# Mainboard.net
KiCad netlist of a schematic drawn in EAGLE
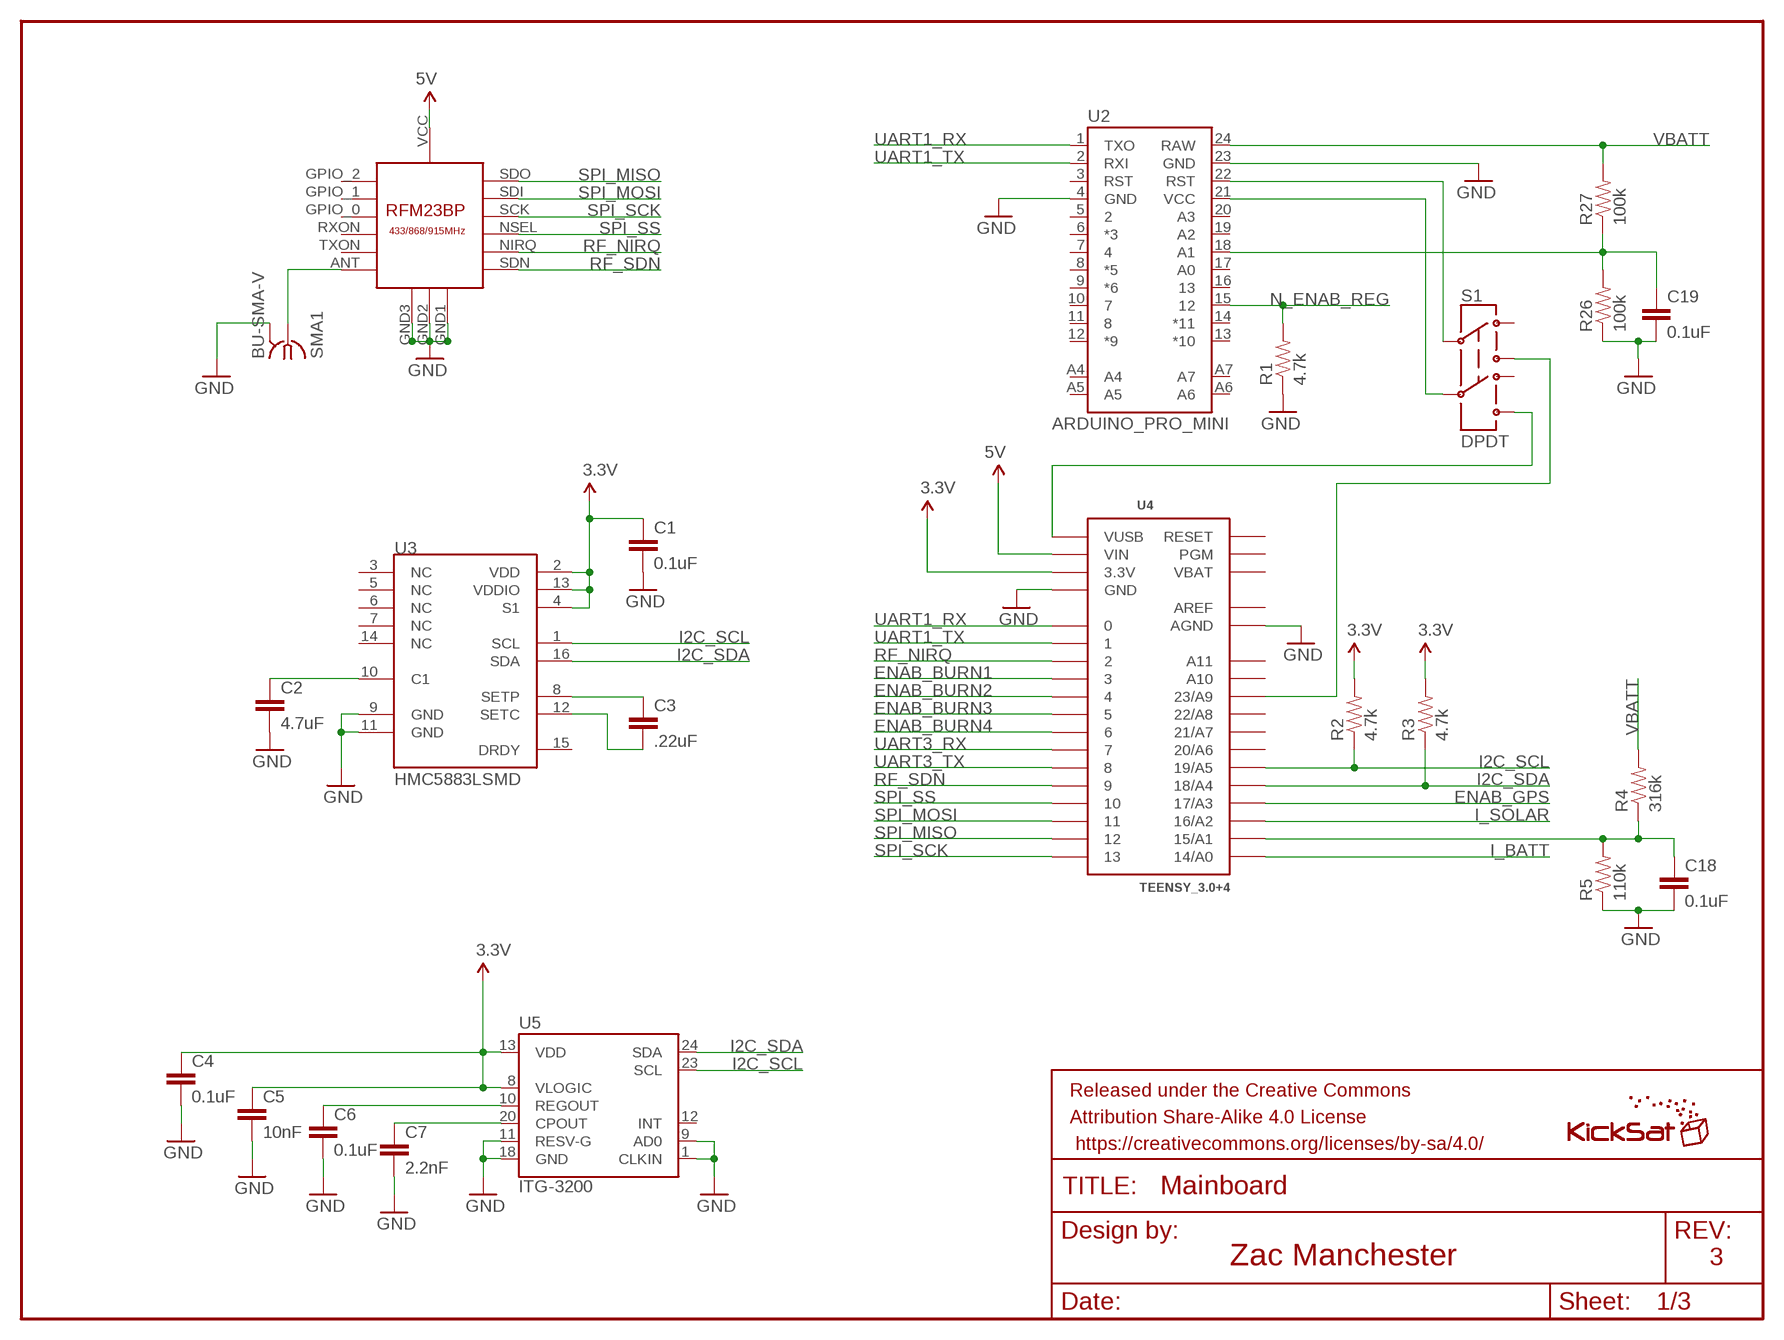
[diagram p0: schematic, sheet 1]
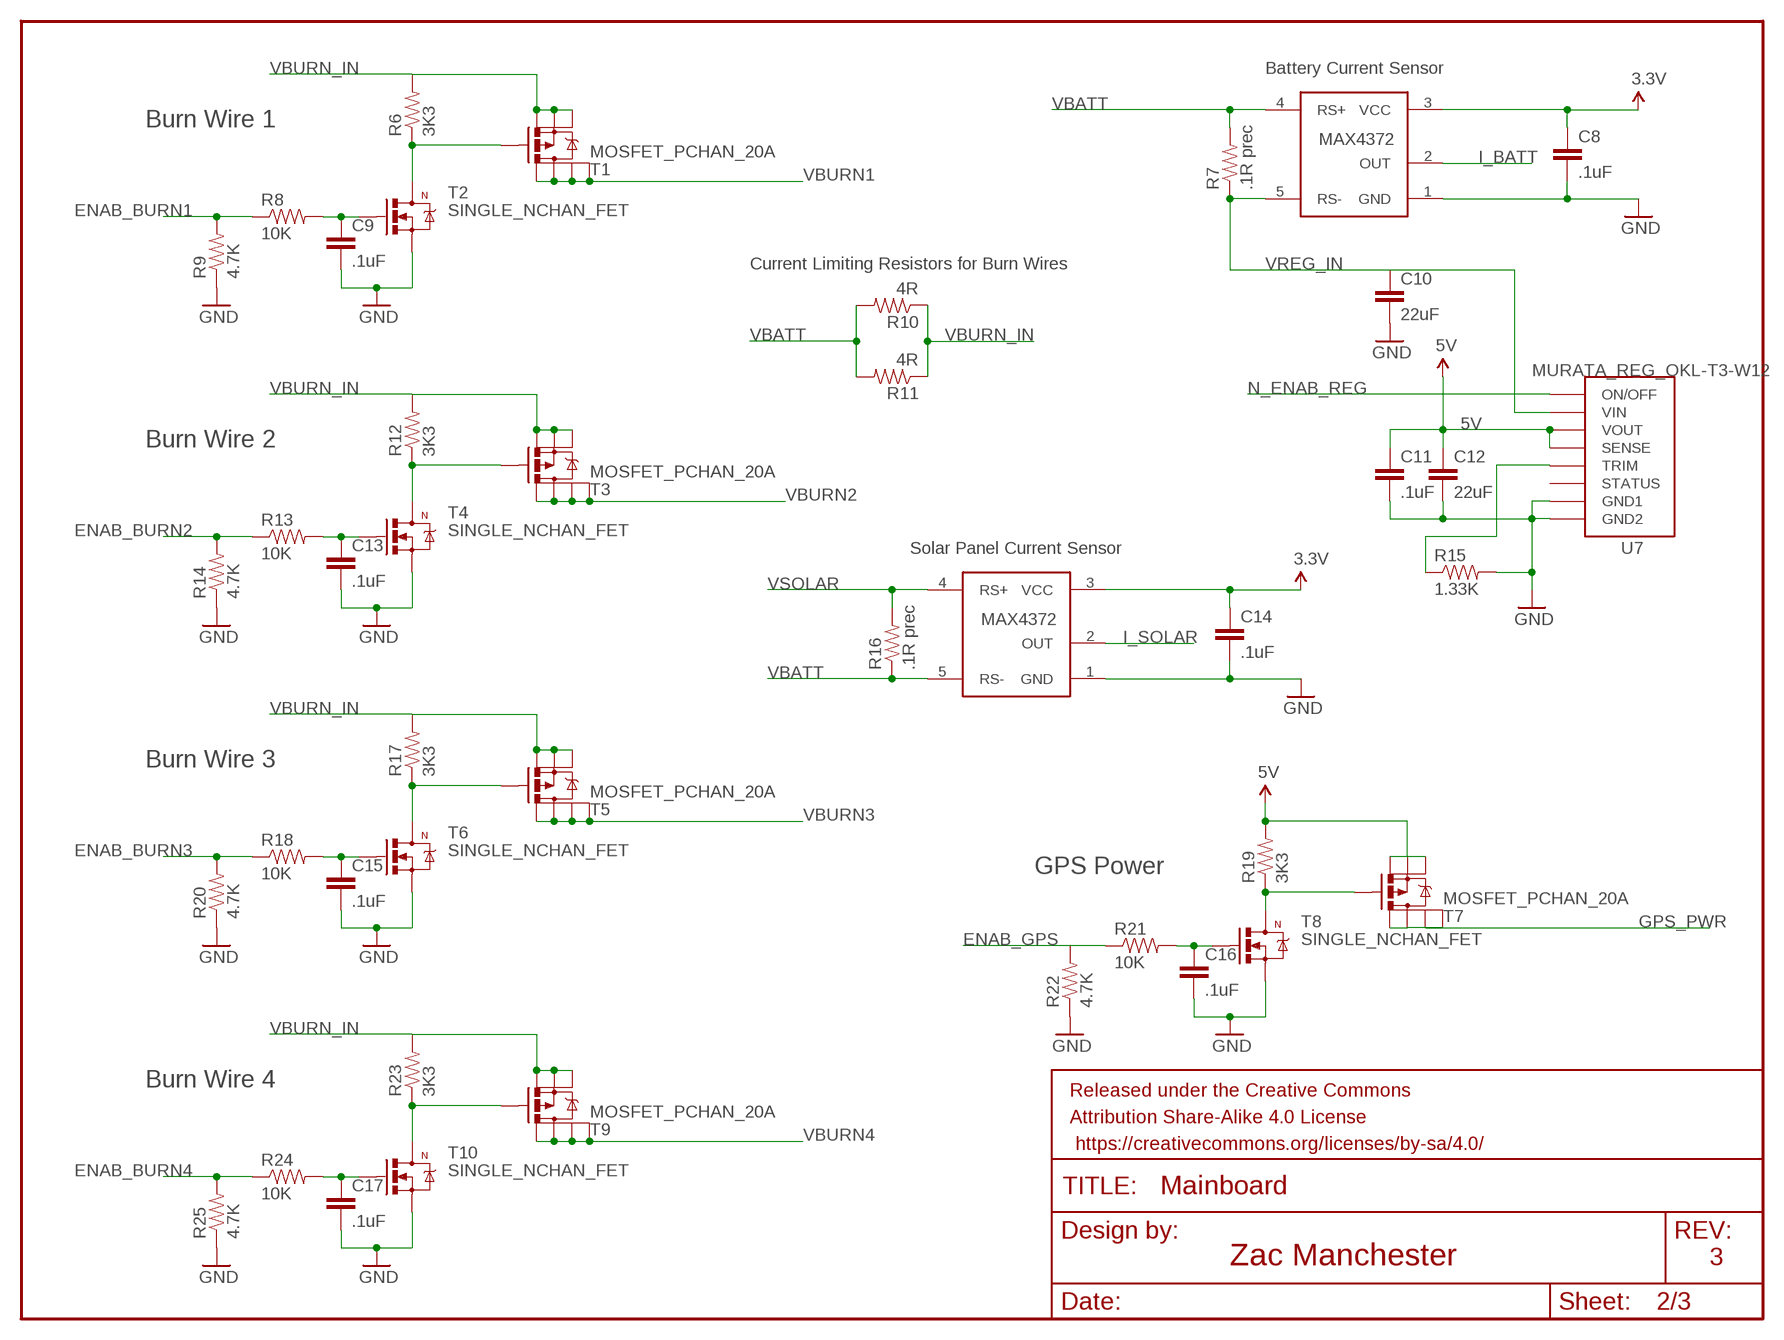
[diagram p1: schematic, sheet 2]
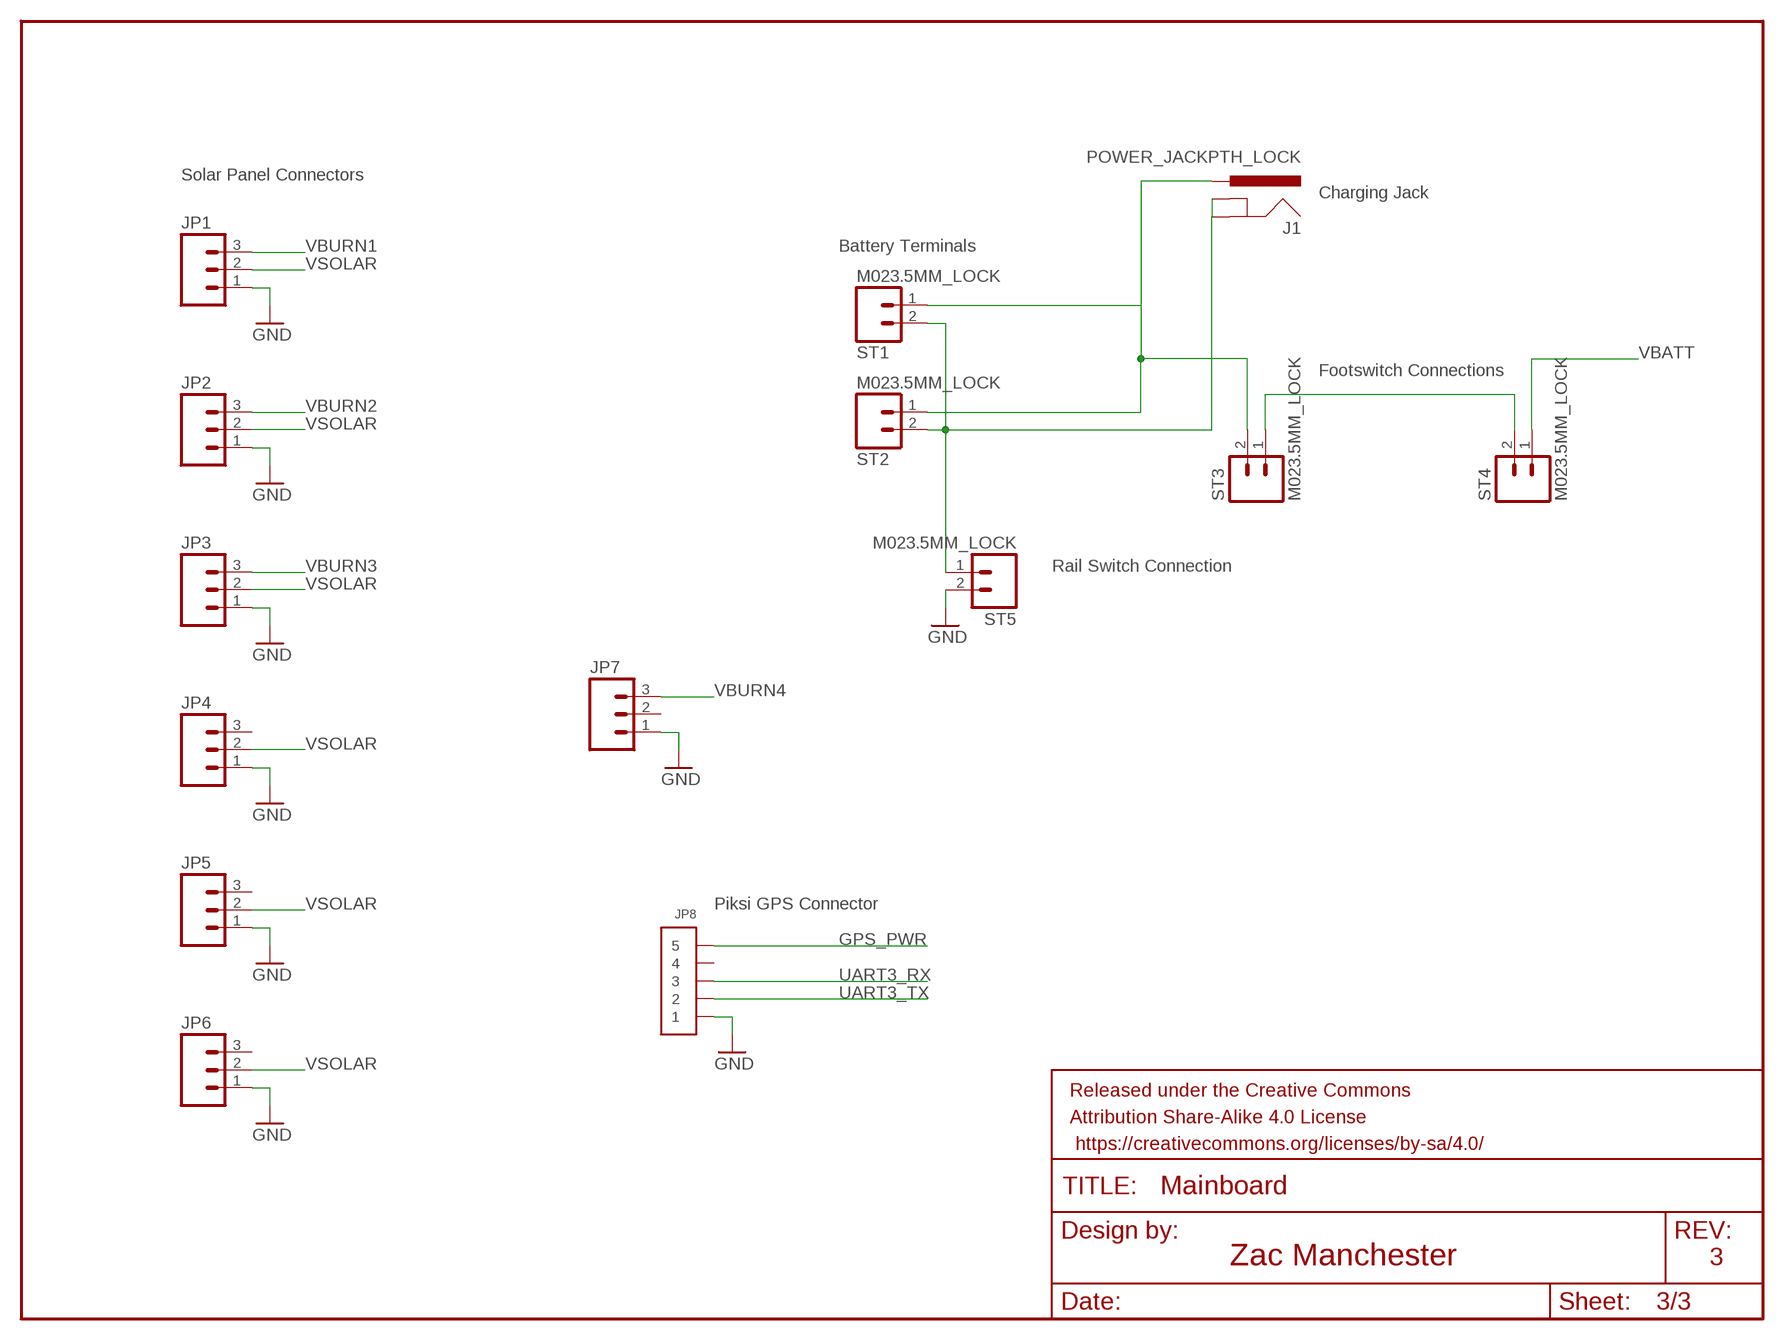
[diagram p2: schematic, sheet 3]

(export (version "E")
  (design (tool "Eeschema 10.0.6"))
  (components
    (comp (ref "C8")
      (value ".1uF")
      (footprint "eagle-import:0805")
      (libsource (lib "eagle-import") (part "CAP0805"))
    )
    (comp (ref "C9")
      (value ".1uF")
      (footprint "eagle-import:0805")
      (libsource (lib "eagle-import") (part "CAP0805"))
    )
    (comp (ref "C10")
      (value "22uF")
      (footprint "eagle-import:1206")
      (libsource (lib "eagle-import") (part "CAP1206"))
    )
    (comp (ref "C11")
      (value ".1uF")
      (footprint "eagle-import:0805")
      (libsource (lib "eagle-import") (part "CAP0805"))
    )
    (comp (ref "C12")
      (value "22uF")
      (footprint "eagle-import:1206")
      (libsource (lib "eagle-import") (part "CAP1206"))
    )
    (comp (ref "C13")
      (value ".1uF")
      (footprint "eagle-import:0805")
      (libsource (lib "eagle-import") (part "CAP0805"))
    )
    (comp (ref "C14")
      (value ".1uF")
      (footprint "eagle-import:0805")
      (libsource (lib "eagle-import") (part "CAP0805"))
    )
    (comp (ref "C15")
      (value ".1uF")
      (footprint "eagle-import:0805")
      (libsource (lib "eagle-import") (part "CAP0805"))
    )
    (comp (ref "C16")
      (value ".1uF")
      (footprint "eagle-import:0805")
      (libsource (lib "eagle-import") (part "CAP0805"))
    )
    (comp (ref "C17")
      (value ".1uF")
      (footprint "eagle-import:0805")
      (libsource (lib "eagle-import") (part "CAP0805"))
    )
    (comp (ref "FRAME2")
      (value "FRAME-LETTER")
      (footprint "eagle-import:CREATIVE_COMMONS")
      (libsource (lib "eagle-import") (part "FRAME-LETTER"))
    )
    (comp (ref "R6")
      (value "3K3")
      (footprint "eagle-import:0805")
      (libsource (lib "eagle-import") (part "RESISTOR0805-RES"))
    )
    (comp (ref "R7")
      (value ".1R prec")
      (footprint "eagle-import:0805")
      (libsource (lib "eagle-import") (part "RESISTOR0805-RES"))
    )
    (comp (ref "R8")
      (value "10K")
      (footprint "eagle-import:0805")
      (libsource (lib "eagle-import") (part "RESISTOR0805-RES"))
    )
    (comp (ref "R9")
      (value "4.7K")
      (footprint "eagle-import:0805")
      (libsource (lib "eagle-import") (part "RESISTOR0805-RES"))
    )
    (comp (ref "R10")
      (value "4R")
      (footprint "eagle-import:R2512")
      (libsource (lib "eagle-import") (part "RESISTOR2512"))
    )
    (comp (ref "R11")
      (value "4R")
      (footprint "eagle-import:R2512")
      (libsource (lib "eagle-import") (part "RESISTOR2512"))
    )
    (comp (ref "R12")
      (value "3K3")
      (footprint "eagle-import:0805")
      (libsource (lib "eagle-import") (part "RESISTOR0805-RES"))
    )
    (comp (ref "R13")
      (value "10K")
      (footprint "eagle-import:0805")
      (libsource (lib "eagle-import") (part "RESISTOR0805-RES"))
    )
    (comp (ref "R14")
      (value "4.7K")
      (footprint "eagle-import:0805")
      (libsource (lib "eagle-import") (part "RESISTOR0805-RES"))
    )
    (comp (ref "R15")
      (value "1.33K")
      (footprint "eagle-import:0805")
      (libsource (lib "eagle-import") (part "RESISTOR0805-RES"))
    )
    (comp (ref "R16")
      (value ".1R prec")
      (footprint "eagle-import:0805")
      (libsource (lib "eagle-import") (part "RESISTOR0805-RES"))
    )
    (comp (ref "R17")
      (value "3K3")
      (footprint "eagle-import:0805")
      (libsource (lib "eagle-import") (part "RESISTOR0805-RES"))
    )
    (comp (ref "R18")
      (value "10K")
      (footprint "eagle-import:0805")
      (libsource (lib "eagle-import") (part "RESISTOR0805-RES"))
    )
    (comp (ref "R19")
      (value "3K3")
      (footprint "eagle-import:0805")
      (libsource (lib "eagle-import") (part "RESISTOR0805-RES"))
    )
    (comp (ref "R20")
      (value "4.7K")
      (footprint "eagle-import:0805")
      (libsource (lib "eagle-import") (part "RESISTOR0805-RES"))
    )
    (comp (ref "R21")
      (value "10K")
      (footprint "eagle-import:0805")
      (libsource (lib "eagle-import") (part "RESISTOR0805-RES"))
    )
    (comp (ref "R22")
      (value "4.7K")
      (footprint "eagle-import:0805")
      (libsource (lib "eagle-import") (part "RESISTOR0805-RES"))
    )
    (comp (ref "R23")
      (value "3K3")
      (footprint "eagle-import:0805")
      (libsource (lib "eagle-import") (part "RESISTOR0805-RES"))
    )
    (comp (ref "R24")
      (value "10K")
      (footprint "eagle-import:0805")
      (libsource (lib "eagle-import") (part "RESISTOR0805-RES"))
    )
    (comp (ref "R25")
      (value "4.7K")
      (footprint "eagle-import:0805")
      (libsource (lib "eagle-import") (part "RESISTOR0805-RES"))
    )
    (comp (ref "T1")
      (value "MOSFET_PCHAN_20A")
      (footprint "eagle-import:SO8")
      (libsource (lib "eagle-import") (part "MOSFET_PCHAN_20A"))
    )
    (comp (ref "T2")
      (value "SINGLE_NCHAN_FET")
      (footprint "eagle-import:SOT23-3")
      (libsource (lib "eagle-import") (part "SINGLE_NCHAN_FET"))
    )
    (comp (ref "T3")
      (value "MOSFET_PCHAN_20A")
      (footprint "eagle-import:SO8")
      (libsource (lib "eagle-import") (part "MOSFET_PCHAN_20A"))
    )
    (comp (ref "T4")
      (value "SINGLE_NCHAN_FET")
      (footprint "eagle-import:SOT23-3")
      (libsource (lib "eagle-import") (part "SINGLE_NCHAN_FET"))
    )
    (comp (ref "T5")
      (value "MOSFET_PCHAN_20A")
      (footprint "eagle-import:SO8")
      (libsource (lib "eagle-import") (part "MOSFET_PCHAN_20A"))
    )
    (comp (ref "T6")
      (value "SINGLE_NCHAN_FET")
      (footprint "eagle-import:SOT23-3")
      (libsource (lib "eagle-import") (part "SINGLE_NCHAN_FET"))
    )
    (comp (ref "T7")
      (value "MOSFET_PCHAN_20A")
      (footprint "eagle-import:SO8")
      (libsource (lib "eagle-import") (part "MOSFET_PCHAN_20A"))
    )
    (comp (ref "T8")
      (value "SINGLE_NCHAN_FET")
      (footprint "eagle-import:SOT23-3")
      (libsource (lib "eagle-import") (part "SINGLE_NCHAN_FET"))
    )
    (comp (ref "T9")
      (value "MOSFET_PCHAN_20A")
      (footprint "eagle-import:SO8")
      (libsource (lib "eagle-import") (part "MOSFET_PCHAN_20A"))
    )
    (comp (ref "T10")
      (value "SINGLE_NCHAN_FET")
      (footprint "eagle-import:SOT23-3")
      (libsource (lib "eagle-import") (part "SINGLE_NCHAN_FET"))
    )
    (comp (ref "U6")
      (value "CURRENT_MAX4372")
      (footprint "eagle-import:SOT23-5")
      (libsource (lib "eagle-import") (part "CURRENT_MAX4372"))
    )
    (comp (ref "U7")
      (value "MURATA_REG_OKL-T3-W12")
      (footprint "eagle-import:MURATA_REG_OKL-T6-W12")
      (libsource (lib "eagle-import") (part "MURATA_REG_OKL-T6-W12"))
    )
    (comp (ref "U8")
      (value "CURRENT_MAX4372")
      (footprint "eagle-import:SOT23-5")
      (libsource (lib "eagle-import") (part "CURRENT_MAX4372"))
    )
    (comp (ref "C1")
      (value "0.1uF")
      (footprint "eagle-import:0805")
      (libsource (lib "eagle-import") (part "CAP0805"))
    )
    (comp (ref "C2")
      (value "4.7uF")
      (footprint "eagle-import:0805")
      (libsource (lib "eagle-import") (part "CAP0805"))
    )
    (comp (ref "C3")
      (value ".22uF")
      (footprint "eagle-import:0805")
      (libsource (lib "eagle-import") (part "CAP0805"))
    )
    (comp (ref "C4")
      (value "0.1uF")
      (footprint "eagle-import:0805")
      (libsource (lib "eagle-import") (part "CAP0805"))
    )
    (comp (ref "C5")
      (value "10nF")
      (footprint "eagle-import:0805")
      (libsource (lib "eagle-import") (part "CAP0805"))
    )
    (comp (ref "C6")
      (value "0.1uF")
      (footprint "eagle-import:0805")
      (libsource (lib "eagle-import") (part "CAP0805"))
    )
    (comp (ref "C7")
      (value "2.2nF")
      (footprint "eagle-import:0805")
      (libsource (lib "eagle-import") (part "CAP0805"))
    )
    (comp (ref "C18")
      (value "0.1uF")
      (footprint "eagle-import:0805")
      (libsource (lib "eagle-import") (part "CAP0805"))
    )
    (comp (ref "C19")
      (value "0.1uF")
      (footprint "eagle-import:0805")
      (libsource (lib "eagle-import") (part "CAP0805"))
    )
    (comp (ref "FRAME1")
      (value "FRAME-LETTER")
      (footprint "eagle-import:CREATIVE_COMMONS")
      (libsource (lib "eagle-import") (part "FRAME-LETTER"))
    )
    (comp (ref "R1")
      (value "4.7k")
      (footprint "eagle-import:0805")
      (libsource (lib "eagle-import") (part "RESISTOR0805-RES"))
    )
    (comp (ref "R2")
      (value "4.7k")
      (footprint "eagle-import:0805")
      (libsource (lib "eagle-import") (part "RESISTOR0805-RES"))
    )
    (comp (ref "R3")
      (value "4.7k")
      (footprint "eagle-import:0805")
      (libsource (lib "eagle-import") (part "RESISTOR0805-RES"))
    )
    (comp (ref "R4")
      (value "316k")
      (footprint "eagle-import:0805")
      (libsource (lib "eagle-import") (part "RESISTOR0805-RES"))
    )
    (comp (ref "R5")
      (value "110k")
      (footprint "eagle-import:0805")
      (libsource (lib "eagle-import") (part "RESISTOR0805-RES"))
    )
    (comp (ref "R26")
      (value "100k")
      (footprint "eagle-import:0805")
      (libsource (lib "eagle-import") (part "RESISTOR0805-RES"))
    )
    (comp (ref "R27")
      (value "100k")
      (footprint "eagle-import:0805")
      (libsource (lib "eagle-import") (part "RESISTOR0805-RES"))
    )
    (comp (ref "S1")
      (value "DPDT")
      (footprint "eagle-import:AYZ0202")
      (libsource (lib "eagle-import") (part "SWITCH-DPDTAYZ0202"))
    )
    (comp (ref "SMA1")
      (value "BU-SMA-V")
      (footprint "eagle-import:BU-SMA-V")
      (libsource (lib "eagle-import") (part "BU-SMA-V"))
    )
    (comp (ref "U$3")
      (value "KICKSAT_LOGO")
      (footprint "eagle-import:KICKSAT_LOGO")
      (libsource (lib "eagle-import") (part "KICKSAT_LOGO"))
    )
    (comp (ref "U1")
      (value "RFM23BP")
      (footprint "eagle-import:RFM23BP")
      (libsource (lib "eagle-import") (part "RFM23BP"))
    )
    (comp (ref "U2")
      (value "ARDUINO_PRO_MINI")
      (footprint "eagle-import:ARDUINO_PRO_MINI")
      (libsource (lib "eagle-import") (part "ARDUINO_PRO_MINI"))
    )
    (comp (ref "U3")
      (value "HMC5883LSMD")
      (footprint "eagle-import:16LPCC")
      (libsource (lib "eagle-import") (part "HMC5883LSMD"))
    )
    (comp (ref "U4")
      (value "TEENSY_3.0+4")
      (footprint "eagle-import:TEENSY_3.0+4")
      (libsource (lib "eagle-import") (part "TEENSY_3.0+4"))
    )
    (comp (ref "U5")
      (value "ITG-3200")
      (footprint "eagle-import:QFN-24")
      (libsource (lib "eagle-import") (part "ITG-3200"))
    )
    (comp (ref "FRAME3")
      (value "FRAME-LETTER")
      (footprint "eagle-import:CREATIVE_COMMONS")
      (libsource (lib "eagle-import") (part "FRAME-LETTER"))
    )
    (comp (ref "J1")
      (value "POWER_JACKPTH_LOCK")
      (footprint "eagle-import:POWER_JACK_PTH_LOCK")
      (libsource (lib "eagle-import") (part "POWER_JACKPTH_LOCK"))
    )
    (comp (ref "JP1")
      (value "M03POLAR_LOCK")
      (footprint "eagle-import:MOLEX-1X3_LOCK")
      (libsource (lib "eagle-import") (part "M03POLAR_LOCK"))
    )
    (comp (ref "JP2")
      (value "M03POLAR_LOCK")
      (footprint "eagle-import:MOLEX-1X3_LOCK")
      (libsource (lib "eagle-import") (part "M03POLAR_LOCK"))
    )
    (comp (ref "JP3")
      (value "M03POLAR_LOCK")
      (footprint "eagle-import:MOLEX-1X3_LOCK")
      (libsource (lib "eagle-import") (part "M03POLAR_LOCK"))
    )
    (comp (ref "JP4")
      (value "M03POLAR_LOCK")
      (footprint "eagle-import:MOLEX-1X3_LOCK")
      (libsource (lib "eagle-import") (part "M03POLAR_LOCK"))
    )
    (comp (ref "JP5")
      (value "M03POLAR_LOCK")
      (footprint "eagle-import:MOLEX-1X3_LOCK")
      (libsource (lib "eagle-import") (part "M03POLAR_LOCK"))
    )
    (comp (ref "JP6")
      (value "M03POLAR_LOCK")
      (footprint "eagle-import:MOLEX-1X3_LOCK")
      (libsource (lib "eagle-import") (part "M03POLAR_LOCK"))
    )
    (comp (ref "JP7")
      (value "M03POLAR_LOCK")
      (footprint "eagle-import:MOLEX-1X3_LOCK")
      (libsource (lib "eagle-import") (part "M03POLAR_LOCK"))
    )
    (comp (ref "JP8")
      (value "CONN_5-1-53261")
      (footprint "eagle-import:PB-53261-05")
      (libsource (lib "eagle-import") (part "CONN_5-1-53261"))
    )
    (comp (ref "ST1")
      (value "M023.5MM_LOCK")
      (footprint "eagle-import:SCREWTERMINAL-3.5MM-2_LOCK")
      (libsource (lib "eagle-import") (part "M023.5MM_LOCK"))
    )
    (comp (ref "ST2")
      (value "M023.5MM_LOCK")
      (footprint "eagle-import:SCREWTERMINAL-3.5MM-2_LOCK")
      (libsource (lib "eagle-import") (part "M023.5MM_LOCK"))
    )
    (comp (ref "ST3")
      (value "M023.5MM_LOCK")
      (footprint "eagle-import:SCREWTERMINAL-3.5MM-2_LOCK")
      (libsource (lib "eagle-import") (part "M023.5MM_LOCK"))
    )
    (comp (ref "ST4")
      (value "M023.5MM_LOCK")
      (footprint "eagle-import:SCREWTERMINAL-3.5MM-2_LOCK")
      (libsource (lib "eagle-import") (part "M023.5MM_LOCK"))
    )
    (comp (ref "ST5")
      (value "M023.5MM_LOCK")
      (footprint "eagle-import:SCREWTERMINAL-3.5MM-2_LOCK")
      (libsource (lib "eagle-import") (part "M023.5MM_LOCK"))
    )
  )
  (nets
    (net (code "1") (name "3.3V") (class "Default")
      (node (ref "C1") (pin "1") (pinfunction "1_1") (pintype "passive"))
      (node (ref "C14") (pin "1") (pinfunction "1_1") (pintype "passive"))
      (node (ref "C4") (pin "1") (pinfunction "1_1") (pintype "passive"))
      (node (ref "C5") (pin "1") (pinfunction "1_1") (pintype "passive"))
      (node (ref "C8") (pin "1") (pinfunction "1_1") (pintype "passive"))
      (node (ref "R2") (pin "2") (pinfunction "2_2") (pintype "passive"))
      (node (ref "R3") (pin "2") (pinfunction "2_2") (pintype "passive"))
      (node (ref "U3") (pin "13") (pinfunction "VDDIO_13") (pintype "bidirectional"))
      (node (ref "U3") (pin "2") (pinfunction "VDD_2") (pintype "bidirectional"))
      (node (ref "U3") (pin "4") (pinfunction "S1_4") (pintype "bidirectional"))
      (node (ref "U4") (pin "3.3V") (pinfunction "3.3V_3.3V") (pintype "power_in"))
      (node (ref "U4") (pin "3.3V1") (pinfunction "3.3V_3.3V1") (pintype "power_in"))
      (node (ref "U5") (pin "13") (pinfunction "VDD_13") (pintype "bidirectional"))
      (node (ref "U5") (pin "8") (pinfunction "VLOGIC_8") (pintype "bidirectional"))
      (node (ref "U6") (pin "3") (pinfunction "VCC_3") (pintype "bidirectional"))
      (node (ref "U8") (pin "3") (pinfunction "VCC_3") (pintype "bidirectional"))
    )
    (net (code "2") (name "5V") (class "Default")
      (node (ref "C11") (pin "1") (pinfunction "1_1") (pintype "passive"))
      (node (ref "C12") (pin "1") (pinfunction "1_1") (pintype "passive"))
      (node (ref "R19") (pin "2") (pinfunction "2_2") (pintype "passive"))
      (node (ref "T7") (pin "1") (pinfunction "S_1") (pintype "passive"))
      (node (ref "T7") (pin "2") (pinfunction "S_2") (pintype "passive"))
      (node (ref "T7") (pin "3") (pinfunction "S_3") (pintype "passive"))
      (node (ref "U1") (pin "VCC") (pinfunction "VCC_VCC") (pintype "power_in"))
      (node (ref "U4") (pin "VIN") (pinfunction "VIN_VIN") (pintype "power_in"))
      (node (ref "U7") (pin "4") (pinfunction "VOUT_4") (pintype "bidirectional"))
      (node (ref "U7") (pin "5") (pinfunction "SENSE_5") (pintype "bidirectional"))
    )
    (net (code "3") (name "AREF") (class "Default")
      (node (ref "U4") (pin "AREF") (pinfunction "AREF_AREF") (pintype "power_in"))
    )
    (net (code "4") (name "ENAB_BURN1") (class "Default")
      (node (ref "R8") (pin "1") (pinfunction "1_1") (pintype "passive"))
      (node (ref "R9") (pin "2") (pinfunction "2_2") (pintype "passive"))
      (node (ref "U4") (pin "3") (pinfunction "3_3") (pintype "bidirectional"))
    )
    (net (code "5") (name "ENAB_BURN2") (class "Default")
      (node (ref "R13") (pin "1") (pinfunction "1_1") (pintype "passive"))
      (node (ref "R14") (pin "2") (pinfunction "2_2") (pintype "passive"))
      (node (ref "U4") (pin "4") (pinfunction "4_4") (pintype "bidirectional"))
    )
    (net (code "6") (name "ENAB_BURN3") (class "Default")
      (node (ref "R18") (pin "1") (pinfunction "1_1") (pintype "passive"))
      (node (ref "R20") (pin "2") (pinfunction "2_2") (pintype "passive"))
      (node (ref "U4") (pin "5") (pinfunction "5_5") (pintype "bidirectional"))
    )
    (net (code "7") (name "ENAB_BURN4") (class "Default")
      (node (ref "R24") (pin "1") (pinfunction "1_1") (pintype "passive"))
      (node (ref "R25") (pin "2") (pinfunction "2_2") (pintype "passive"))
      (node (ref "U4") (pin "6") (pinfunction "6_6") (pintype "bidirectional"))
    )
    (net (code "8") (name "ENAB_GPS") (class "Default")
      (node (ref "R21") (pin "1") (pinfunction "1_1") (pintype "passive"))
      (node (ref "R22") (pin "2") (pinfunction "2_2") (pintype "passive"))
      (node (ref "U4") (pin "17/A3") (pinfunction "17/A3_17/A3") (pintype "bidirectional"))
    )
    (net (code "9") (name "GND") (class "Default")
      (node (ref "C1") (pin "2") (pinfunction "2_2") (pintype "passive"))
      (node (ref "C10") (pin "2") (pinfunction "2_2") (pintype "passive"))
      (node (ref "C11") (pin "2") (pinfunction "2_2") (pintype "passive"))
      (node (ref "C12") (pin "2") (pinfunction "2_2") (pintype "passive"))
      (node (ref "C13") (pin "2") (pinfunction "2_2") (pintype "passive"))
      (node (ref "C14") (pin "2") (pinfunction "2_2") (pintype "passive"))
      (node (ref "C15") (pin "2") (pinfunction "2_2") (pintype "passive"))
      (node (ref "C16") (pin "2") (pinfunction "2_2") (pintype "passive"))
      (node (ref "C17") (pin "2") (pinfunction "2_2") (pintype "passive"))
      (node (ref "C18") (pin "2") (pinfunction "2_2") (pintype "passive"))
      (node (ref "C19") (pin "2") (pinfunction "2_2") (pintype "passive"))
      (node (ref "C2") (pin "2") (pinfunction "2_2") (pintype "passive"))
      (node (ref "C4") (pin "2") (pinfunction "2_2") (pintype "passive"))
      (node (ref "C5") (pin "2") (pinfunction "2_2") (pintype "passive"))
      (node (ref "C6") (pin "2") (pinfunction "2_2") (pintype "passive"))
      (node (ref "C7") (pin "2") (pinfunction "2_2") (pintype "passive"))
      (node (ref "C8") (pin "2") (pinfunction "2_2") (pintype "passive"))
      (node (ref "C9") (pin "2") (pinfunction "2_2") (pintype "passive"))
      (node (ref "JP1") (pin "1") (pinfunction "1_1") (pintype "passive"))
      (node (ref "JP2") (pin "1") (pinfunction "1_1") (pintype "passive"))
      (node (ref "JP3") (pin "1") (pinfunction "1_1") (pintype "passive"))
      (node (ref "JP4") (pin "1") (pinfunction "1_1") (pintype "passive"))
      (node (ref "JP5") (pin "1") (pinfunction "1_1") (pintype "passive"))
      (node (ref "JP6") (pin "1") (pinfunction "1_1") (pintype "passive"))
      (node (ref "JP7") (pin "1") (pinfunction "1_1") (pintype "passive"))
      (node (ref "JP8") (pin "1") (pinfunction "1_1") (pintype "bidirectional"))
      (node (ref "R1") (pin "1") (pinfunction "1_1") (pintype "passive"))
      (node (ref "R14") (pin "1") (pinfunction "1_1") (pintype "passive"))
      (node (ref "R15") (pin "2") (pinfunction "2_2") (pintype "passive"))
      (node (ref "R20") (pin "1") (pinfunction "1_1") (pintype "passive"))
      (node (ref "R22") (pin "1") (pinfunction "1_1") (pintype "passive"))
      (node (ref "R25") (pin "1") (pinfunction "1_1") (pintype "passive"))
      (node (ref "R26") (pin "1") (pinfunction "1_1") (pintype "passive"))
      (node (ref "R5") (pin "1") (pinfunction "1_1") (pintype "passive"))
      (node (ref "R9") (pin "1") (pinfunction "1_1") (pintype "passive"))
      (node (ref "SMA1") (pin "2") (pinfunction "2_2") (pintype "passive"))
      (node (ref "SMA1") (pin "3") (pinfunction "2_3") (pintype "passive"))
      (node (ref "SMA1") (pin "4") (pinfunction "2_4") (pintype "passive"))
      (node (ref "SMA1") (pin "5") (pinfunction "2_5") (pintype "passive"))
      (node (ref "ST5") (pin "2") (pinfunction "2_2") (pintype "passive"))
      (node (ref "T10") (pin "2") (pinfunction "S_2") (pintype "passive"))
      (node (ref "T2") (pin "2") (pinfunction "S_2") (pintype "passive"))
      (node (ref "T4") (pin "2") (pinfunction "S_2") (pintype "passive"))
      (node (ref "T6") (pin "2") (pinfunction "S_2") (pintype "passive"))
      (node (ref "T8") (pin "2") (pinfunction "S_2") (pintype "passive"))
      (node (ref "U1") (pin "GND1") (pinfunction "GND1_GND1") (pintype "power_in"))
      (node (ref "U1") (pin "GND2") (pinfunction "GND2_GND2") (pintype "power_in"))
      (node (ref "U1") (pin "GND3") (pinfunction "GND3_GND3") (pintype "power_in"))
      (node (ref "U2") (pin "23") (pinfunction "GND_23") (pintype "bidirectional"))
      (node (ref "U2") (pin "4") (pinfunction "GND_4") (pintype "bidirectional"))
      (node (ref "U3") (pin "11") (pinfunction "GND_11") (pintype "bidirectional"))
      (node (ref "U3") (pin "9") (pinfunction "GND_9") (pintype "bidirectional"))
      (node (ref "U4") (pin "AGND") (pinfunction "AGND_AGND") (pintype "power_in"))
      (node (ref "U4") (pin "GND") (pinfunction "GND_GND") (pintype "power_in"))
      (node (ref "U4") (pin "GND1") (pinfunction "GND_GND1") (pintype "power_in"))
      (node (ref "U5") (pin "1") (pinfunction "CLKIN_1") (pintype "bidirectional"))
      (node (ref "U5") (pin "11") (pinfunction "RESV-G_11") (pintype "bidirectional"))
      (node (ref "U5") (pin "18") (pinfunction "GND_18") (pintype "bidirectional"))
      (node (ref "U5") (pin "9") (pinfunction "AD0_9") (pintype "bidirectional"))
      (node (ref "U6") (pin "1") (pinfunction "GND_1") (pintype "bidirectional"))
      (node (ref "U7") (pin "3") (pinfunction "GND1_3") (pintype "bidirectional"))
      (node (ref "U7") (pin "7") (pinfunction "GND2_7") (pintype "bidirectional"))
      (node (ref "U8") (pin "1") (pinfunction "GND_1") (pintype "bidirectional"))
    )
    (net (code "10") (name "GPS_PWR") (class "Default")
      (node (ref "JP8") (pin "5") (pinfunction "5_5") (pintype "bidirectional"))
      (node (ref "T7") (pin "5") (pinfunction "D_5") (pintype "passive"))
      (node (ref "T7") (pin "6") (pinfunction "D_6") (pintype "passive"))
      (node (ref "T7") (pin "7") (pinfunction "D_7") (pintype "passive"))
      (node (ref "T7") (pin "8") (pinfunction "D_8") (pintype "passive"))
    )
    (net (code "11") (name "I2C_SCL") (class "Default")
      (node (ref "R2") (pin "1") (pinfunction "1_1") (pintype "passive"))
      (node (ref "U3") (pin "1") (pinfunction "SCL_1") (pintype "bidirectional"))
      (node (ref "U4") (pin "19/A5") (pinfunction "19/A5_19/A5") (pintype "bidirectional"))
      (node (ref "U5") (pin "23") (pinfunction "SCL_23") (pintype "bidirectional"))
    )
    (net (code "12") (name "I2C_SDA") (class "Default")
      (node (ref "R3") (pin "1") (pinfunction "1_1") (pintype "passive"))
      (node (ref "U3") (pin "16") (pinfunction "SDA_16") (pintype "bidirectional"))
      (node (ref "U4") (pin "18/A4") (pinfunction "18/A4_18/A4") (pintype "bidirectional"))
      (node (ref "U5") (pin "24") (pinfunction "SDA_24") (pintype "bidirectional"))
    )
    (net (code "13") (name "I_BATT") (class "Default")
      (node (ref "U4") (pin "14/A0") (pinfunction "14/A0_14/A0") (pintype "bidirectional"))
      (node (ref "U6") (pin "2") (pinfunction "OUT_2") (pintype "bidirectional"))
    )
    (net (code "14") (name "I_SOLAR") (class "Default")
      (node (ref "U4") (pin "16/A2") (pinfunction "16/A2_16/A2") (pintype "bidirectional"))
      (node (ref "U8") (pin "2") (pinfunction "OUT_2") (pintype "bidirectional"))
    )
    (net (code "15") (name "N_ENAB_REG") (class "Default")
      (node (ref "R1") (pin "2") (pinfunction "2_2") (pintype "passive"))
      (node (ref "U2") (pin "15") (pinfunction "12_15") (pintype "bidirectional"))
      (node (ref "U7") (pin "1") (pinfunction "ON/OFF_1") (pintype "bidirectional"))
    )
    (net (code "16") (name "Net-(C18-Pad1)") (class "Default")
      (node (ref "C18") (pin "1") (pinfunction "1_1") (pintype "passive"))
      (node (ref "R4") (pin "1") (pinfunction "1_1") (pintype "passive"))
      (node (ref "R5") (pin "2") (pinfunction "2_2") (pintype "passive"))
      (node (ref "U4") (pin "15/A1") (pinfunction "15/A1_15/A1") (pintype "bidirectional"))
    )
    (net (code "17") (name "Net-(J1-PadGND)") (class "Default")
      (node (ref "J1") (pin "GND") (pinfunction "GND_GND") (pintype "bidirectional"))
      (node (ref "J1") (pin "GNDBREAK") (pinfunction "GNDBREAK_GNDBREAK") (pintype "bidirectional"))
      (node (ref "ST1") (pin "2") (pinfunction "2_2") (pintype "passive"))
      (node (ref "ST2") (pin "2") (pinfunction "2_2") (pintype "passive"))
      (node (ref "ST5") (pin "1") (pinfunction "1_1") (pintype "passive"))
    )
    (net (code "18") (name "Net-(J1-PadPWR)") (class "Default")
      (node (ref "J1") (pin "PWR") (pinfunction "PWR_PWR") (pintype "bidirectional"))
      (node (ref "ST1") (pin "1") (pinfunction "1_1") (pintype "passive"))
      (node (ref "ST2") (pin "1") (pinfunction "1_1") (pintype "passive"))
      (node (ref "ST3") (pin "2") (pinfunction "2_2") (pintype "passive"))
    )
    (net (code "19") (name "Net-(S1-Pad2)") (class "Default")
      (node (ref "S1") (pin "2") (pinfunction "2_2") (pintype "bidirectional"))
      (node (ref "U2") (pin "22") (pinfunction "RST_22") (pintype "bidirectional"))
    )
    (net (code "20") (name "Net-(S1-Pad3)") (class "Default")
      (node (ref "S1") (pin "3") (pinfunction "3_3") (pintype "bidirectional"))
      (node (ref "U4") (pin "23/A9") (pinfunction "23/A9_23/A9") (pintype "bidirectional"))
    )
    (net (code "21") (name "Net-(S1-Pad6)") (class "Default")
      (node (ref "S1") (pin "6") (pinfunction "6_6") (pintype "bidirectional"))
      (node (ref "U4") (pin "VUSB") (pinfunction "VUSB_VUSB") (pintype "power_in"))
    )
    (net (code "22") (name "Net-(SMA1-Pad1)") (class "Default")
      (node (ref "SMA1") (pin "1") (pinfunction "1_1") (pintype "passive"))
      (node (ref "U1") (pin "ANT") (pinfunction "ANT_ANT") (pintype "bidirectional"))
    )
    (net (code "23") (name "Net-(ST3-Pad1)") (class "Default")
      (node (ref "ST3") (pin "1") (pinfunction "1_1") (pintype "passive"))
      (node (ref "ST4") (pin "2") (pinfunction "2_2") (pintype "passive"))
    )
    (net (code "24") (name "Net-(T1-G)") (class "Default")
      (node (ref "R6") (pin "1") (pinfunction "1_1") (pintype "passive"))
      (node (ref "T1") (pin "4") (pinfunction "G_4") (pintype "passive"))
      (node (ref "T2") (pin "3") (pinfunction "D_3") (pintype "passive"))
    )
    (net (code "25") (name "Net-(T2-G)") (class "Default")
      (node (ref "C9") (pin "1") (pinfunction "1_1") (pintype "passive"))
      (node (ref "R8") (pin "2") (pinfunction "2_2") (pintype "passive"))
      (node (ref "T2") (pin "1") (pinfunction "G_1") (pintype "passive"))
    )
    (net (code "26") (name "Net-(T3-G)") (class "Default")
      (node (ref "R12") (pin "1") (pinfunction "1_1") (pintype "passive"))
      (node (ref "T3") (pin "4") (pinfunction "G_4") (pintype "passive"))
      (node (ref "T4") (pin "3") (pinfunction "D_3") (pintype "passive"))
    )
    (net (code "27") (name "Net-(T4-G)") (class "Default")
      (node (ref "C13") (pin "1") (pinfunction "1_1") (pintype "passive"))
      (node (ref "R13") (pin "2") (pinfunction "2_2") (pintype "passive"))
      (node (ref "T4") (pin "1") (pinfunction "G_1") (pintype "passive"))
    )
    (net (code "28") (name "Net-(T5-G)") (class "Default")
      (node (ref "R17") (pin "1") (pinfunction "1_1") (pintype "passive"))
      (node (ref "T5") (pin "4") (pinfunction "G_4") (pintype "passive"))
      (node (ref "T6") (pin "3") (pinfunction "D_3") (pintype "passive"))
    )
    (net (code "29") (name "Net-(T6-G)") (class "Default")
      (node (ref "C15") (pin "1") (pinfunction "1_1") (pintype "passive"))
      (node (ref "R18") (pin "2") (pinfunction "2_2") (pintype "passive"))
      (node (ref "T6") (pin "1") (pinfunction "G_1") (pintype "passive"))
    )
    (net (code "30") (name "Net-(T7-G)") (class "Default")
      (node (ref "R19") (pin "1") (pinfunction "1_1") (pintype "passive"))
      (node (ref "T7") (pin "4") (pinfunction "G_4") (pintype "passive"))
      (node (ref "T8") (pin "3") (pinfunction "D_3") (pintype "passive"))
    )
    (net (code "31") (name "Net-(T8-G)") (class "Default")
      (node (ref "C16") (pin "1") (pinfunction "1_1") (pintype "passive"))
      (node (ref "R21") (pin "2") (pinfunction "2_2") (pintype "passive"))
      (node (ref "T8") (pin "1") (pinfunction "G_1") (pintype "passive"))
    )
    (net (code "32") (name "Net-(T10-D)") (class "Default")
      (node (ref "R23") (pin "1") (pinfunction "1_1") (pintype "passive"))
      (node (ref "T10") (pin "3") (pinfunction "D_3") (pintype "passive"))
      (node (ref "T9") (pin "4") (pinfunction "G_4") (pintype "passive"))
    )
    (net (code "33") (name "Net-(T10-G)") (class "Default")
      (node (ref "C17") (pin "1") (pinfunction "1_1") (pintype "passive"))
      (node (ref "R24") (pin "2") (pinfunction "2_2") (pintype "passive"))
      (node (ref "T10") (pin "1") (pinfunction "G_1") (pintype "passive"))
    )
    (net (code "34") (name "Net-(U2-A1)") (class "Default")
      (node (ref "C19") (pin "1") (pinfunction "1_1") (pintype "passive"))
      (node (ref "R26") (pin "2") (pinfunction "2_2") (pintype "passive"))
      (node (ref "R27") (pin "1") (pinfunction "1_1") (pintype "passive"))
      (node (ref "U2") (pin "18") (pinfunction "A1_18") (pintype "bidirectional"))
    )
    (net (code "35") (name "Net-(U2-VCC)") (class "Default")
      (node (ref "S1") (pin "5") (pinfunction "5_5") (pintype "bidirectional"))
      (node (ref "U2") (pin "21") (pinfunction "VCC_21") (pintype "bidirectional"))
    )
    (net (code "36") (name "Net-(U3-C1)") (class "Default")
      (node (ref "C2") (pin "1") (pinfunction "1_1") (pintype "passive"))
      (node (ref "U3") (pin "10") (pinfunction "C1_10") (pintype "bidirectional"))
    )
    (net (code "37") (name "Net-(U3-SETC)") (class "Default")
      (node (ref "C3") (pin "2") (pinfunction "2_2") (pintype "passive"))
      (node (ref "U3") (pin "12") (pinfunction "SETC_12") (pintype "bidirectional"))
    )
    (net (code "38") (name "Net-(U3-SETP)") (class "Default")
      (node (ref "C3") (pin "1") (pinfunction "1_1") (pintype "passive"))
      (node (ref "U3") (pin "8") (pinfunction "SETP_8") (pintype "bidirectional"))
    )
    (net (code "39") (name "Net-(U5-CPOUT)") (class "Default")
      (node (ref "C7") (pin "1") (pinfunction "1_1") (pintype "passive"))
      (node (ref "U5") (pin "20") (pinfunction "CPOUT_20") (pintype "bidirectional"))
    )
    (net (code "40") (name "Net-(U5-REGOUT)") (class "Default")
      (node (ref "C6") (pin "1") (pinfunction "1_1") (pintype "passive"))
      (node (ref "U5") (pin "10") (pinfunction "REGOUT_10") (pintype "bidirectional"))
    )
    (net (code "41") (name "Net-(U7-TRIM)") (class "Default")
      (node (ref "R15") (pin "1") (pinfunction "1_1") (pintype "passive"))
      (node (ref "U7") (pin "6") (pinfunction "TRIM_6") (pintype "bidirectional"))
    )
    (net (code "42") (name "RF_NIRQ") (class "Default")
      (node (ref "U1") (pin "NIRQ") (pinfunction "NIRQ_NIRQ") (pintype "bidirectional"))
      (node (ref "U4") (pin "2") (pinfunction "2_2") (pintype "bidirectional"))
    )
    (net (code "43") (name "RF_SDN") (class "Default")
      (node (ref "U1") (pin "SDN") (pinfunction "SDN_SDN") (pintype "bidirectional"))
      (node (ref "U4") (pin "9") (pinfunction "9_9") (pintype "bidirectional"))
    )
    (net (code "44") (name "SPI_MISO") (class "Default")
      (node (ref "U1") (pin "SDO") (pinfunction "SDO_SDO") (pintype "bidirectional"))
      (node (ref "U4") (pin "12") (pinfunction "12_12") (pintype "bidirectional"))
    )
    (net (code "45") (name "SPI_MOSI") (class "Default")
      (node (ref "U1") (pin "SDI") (pinfunction "SDI_SDI") (pintype "bidirectional"))
      (node (ref "U4") (pin "11") (pinfunction "11_11") (pintype "bidirectional"))
    )
    (net (code "46") (name "SPI_SCK") (class "Default")
      (node (ref "U1") (pin "SCK") (pinfunction "SCK_SCK") (pintype "bidirectional"))
      (node (ref "U4") (pin "13") (pinfunction "13_13") (pintype "bidirectional"))
    )
    (net (code "47") (name "SPI_SS") (class "Default")
      (node (ref "U1") (pin "NSEL") (pinfunction "NSEL_NSEL") (pintype "bidirectional"))
      (node (ref "U4") (pin "10") (pinfunction "10_10") (pintype "bidirectional"))
    )
    (net (code "48") (name "UART1_RX") (class "Default")
      (node (ref "U2") (pin "1") (pinfunction "TXO_1") (pintype "bidirectional"))
      (node (ref "U4") (pin "0") (pinfunction "0_0") (pintype "bidirectional"))
    )
    (net (code "49") (name "UART1_TX") (class "Default")
      (node (ref "U2") (pin "2") (pinfunction "RXI_2") (pintype "bidirectional"))
      (node (ref "U4") (pin "1") (pinfunction "1_1") (pintype "bidirectional"))
    )
    (net (code "50") (name "UART3_RX") (class "Default")
      (node (ref "JP8") (pin "3") (pinfunction "3_3") (pintype "bidirectional"))
      (node (ref "U4") (pin "7") (pinfunction "7_7") (pintype "bidirectional"))
    )
    (net (code "51") (name "UART3_TX") (class "Default")
      (node (ref "JP8") (pin "2") (pinfunction "2_2") (pintype "bidirectional"))
      (node (ref "U4") (pin "8") (pinfunction "8_8") (pintype "bidirectional"))
    )
    (net (code "52") (name "VBAT") (class "Default")
      (node (ref "U4") (pin "VBAT") (pinfunction "VBAT_VBAT") (pintype "power_in"))
    )
    (net (code "53") (name "VBATT") (class "Default")
      (node (ref "R10") (pin "2") (pinfunction "2_2") (pintype "passive"))
      (node (ref "R11") (pin "2") (pinfunction "2_2") (pintype "passive"))
      (node (ref "R16") (pin "1") (pinfunction "1_1") (pintype "passive"))
      (node (ref "R27") (pin "2") (pinfunction "2_2") (pintype "passive"))
      (node (ref "R4") (pin "2") (pinfunction "2_2") (pintype "passive"))
      (node (ref "R7") (pin "2") (pinfunction "2_2") (pintype "passive"))
      (node (ref "ST4") (pin "1") (pinfunction "1_1") (pintype "passive"))
      (node (ref "U2") (pin "24") (pinfunction "RAW_24") (pintype "bidirectional"))
      (node (ref "U6") (pin "4") (pinfunction "RS+_4") (pintype "bidirectional"))
      (node (ref "U8") (pin "5") (pinfunction "RS-_5") (pintype "bidirectional"))
    )
    (net (code "54") (name "VBURN1") (class "Default")
      (node (ref "JP1") (pin "3") (pinfunction "3_3") (pintype "passive"))
      (node (ref "T1") (pin "5") (pinfunction "D_5") (pintype "passive"))
      (node (ref "T1") (pin "6") (pinfunction "D_6") (pintype "passive"))
      (node (ref "T1") (pin "7") (pinfunction "D_7") (pintype "passive"))
      (node (ref "T1") (pin "8") (pinfunction "D_8") (pintype "passive"))
    )
    (net (code "55") (name "VBURN2") (class "Default")
      (node (ref "JP2") (pin "3") (pinfunction "3_3") (pintype "passive"))
      (node (ref "T3") (pin "5") (pinfunction "D_5") (pintype "passive"))
      (node (ref "T3") (pin "6") (pinfunction "D_6") (pintype "passive"))
      (node (ref "T3") (pin "7") (pinfunction "D_7") (pintype "passive"))
      (node (ref "T3") (pin "8") (pinfunction "D_8") (pintype "passive"))
    )
    (net (code "56") (name "VBURN3") (class "Default")
      (node (ref "JP3") (pin "3") (pinfunction "3_3") (pintype "passive"))
      (node (ref "T5") (pin "5") (pinfunction "D_5") (pintype "passive"))
      (node (ref "T5") (pin "6") (pinfunction "D_6") (pintype "passive"))
      (node (ref "T5") (pin "7") (pinfunction "D_7") (pintype "passive"))
      (node (ref "T5") (pin "8") (pinfunction "D_8") (pintype "passive"))
    )
    (net (code "57") (name "VBURN4") (class "Default")
      (node (ref "JP7") (pin "3") (pinfunction "3_3") (pintype "passive"))
      (node (ref "T9") (pin "5") (pinfunction "D_5") (pintype "passive"))
      (node (ref "T9") (pin "6") (pinfunction "D_6") (pintype "passive"))
      (node (ref "T9") (pin "7") (pinfunction "D_7") (pintype "passive"))
      (node (ref "T9") (pin "8") (pinfunction "D_8") (pintype "passive"))
    )
    (net (code "58") (name "VBURN_IN") (class "Default")
      (node (ref "R10") (pin "1") (pinfunction "1_1") (pintype "passive"))
      (node (ref "R11") (pin "1") (pinfunction "1_1") (pintype "passive"))
      (node (ref "R12") (pin "2") (pinfunction "2_2") (pintype "passive"))
      (node (ref "R17") (pin "2") (pinfunction "2_2") (pintype "passive"))
      (node (ref "R23") (pin "2") (pinfunction "2_2") (pintype "passive"))
      (node (ref "R6") (pin "2") (pinfunction "2_2") (pintype "passive"))
      (node (ref "T1") (pin "1") (pinfunction "S_1") (pintype "passive"))
      (node (ref "T1") (pin "2") (pinfunction "S_2") (pintype "passive"))
      (node (ref "T1") (pin "3") (pinfunction "S_3") (pintype "passive"))
      (node (ref "T3") (pin "1") (pinfunction "S_1") (pintype "passive"))
      (node (ref "T3") (pin "2") (pinfunction "S_2") (pintype "passive"))
      (node (ref "T3") (pin "3") (pinfunction "S_3") (pintype "passive"))
      (node (ref "T5") (pin "1") (pinfunction "S_1") (pintype "passive"))
      (node (ref "T5") (pin "2") (pinfunction "S_2") (pintype "passive"))
      (node (ref "T5") (pin "3") (pinfunction "S_3") (pintype "passive"))
      (node (ref "T9") (pin "1") (pinfunction "S_1") (pintype "passive"))
      (node (ref "T9") (pin "2") (pinfunction "S_2") (pintype "passive"))
      (node (ref "T9") (pin "3") (pinfunction "S_3") (pintype "passive"))
    )
    (net (code "59") (name "VREG_IN") (class "Default")
      (node (ref "C10") (pin "1") (pinfunction "1_1") (pintype "passive"))
      (node (ref "R7") (pin "1") (pinfunction "1_1") (pintype "passive"))
      (node (ref "U6") (pin "5") (pinfunction "RS-_5") (pintype "bidirectional"))
      (node (ref "U7") (pin "2") (pinfunction "VIN_2") (pintype "bidirectional"))
    )
    (net (code "60") (name "VSOLAR") (class "Default")
      (node (ref "JP1") (pin "2") (pinfunction "2_2") (pintype "passive"))
      (node (ref "JP2") (pin "2") (pinfunction "2_2") (pintype "passive"))
      (node (ref "JP3") (pin "2") (pinfunction "2_2") (pintype "passive"))
      (node (ref "JP4") (pin "2") (pinfunction "2_2") (pintype "passive"))
      (node (ref "JP5") (pin "2") (pinfunction "2_2") (pintype "passive"))
      (node (ref "JP6") (pin "2") (pinfunction "2_2") (pintype "passive"))
      (node (ref "R16") (pin "2") (pinfunction "2_2") (pintype "passive"))
      (node (ref "U8") (pin "4") (pinfunction "RS+_4") (pintype "bidirectional"))
    )
    (net (code "61") (name "unconnected-(JP4-Pad3)") (class "Default")
      (node (ref "JP4") (pin "3") (pinfunction "3_3") (pintype "passive"))
    )
    (net (code "62") (name "unconnected-(JP5-Pad3)") (class "Default")
      (node (ref "JP5") (pin "3") (pinfunction "3_3") (pintype "passive"))
    )
    (net (code "63") (name "unconnected-(JP6-Pad3)") (class "Default")
      (node (ref "JP6") (pin "3") (pinfunction "3_3") (pintype "passive"))
    )
    (net (code "64") (name "unconnected-(JP7-Pad2)") (class "Default")
      (node (ref "JP7") (pin "2") (pinfunction "2_2") (pintype "passive"))
    )
    (net (code "65") (name "unconnected-(JP8-Pad4)") (class "Default")
      (node (ref "JP8") (pin "4") (pinfunction "4_4") (pintype "bidirectional"))
    )
    (net (code "66") (name "unconnected-(S1-Pad1)") (class "Default")
      (node (ref "S1") (pin "1") (pinfunction "1_1") (pintype "bidirectional"))
    )
    (net (code "67") (name "unconnected-(S1-Pad4)") (class "Default")
      (node (ref "S1") (pin "4") (pinfunction "4_4") (pintype "bidirectional"))
    )
    (net (code "68") (name "unconnected-(U1-PadGPIO_0)") (class "Default")
      (node (ref "U1") (pin "GPIO_0") (pinfunction "GPIO_0_GPIO_0") (pintype "bidirectional"))
    )
    (net (code "69") (name "unconnected-(U1-PadGPIO_1)") (class "Default")
      (node (ref "U1") (pin "GPIO_1") (pinfunction "GPIO_1_GPIO_1") (pintype "bidirectional"))
    )
    (net (code "70") (name "unconnected-(U1-PadGPIO_2)") (class "Default")
      (node (ref "U1") (pin "GPIO_2") (pinfunction "GPIO_2_GPIO_2") (pintype "bidirectional"))
    )
    (net (code "71") (name "unconnected-(U1-PadRXON)") (class "Default")
      (node (ref "U1") (pin "RXON") (pinfunction "RXON_RXON") (pintype "bidirectional"))
    )
    (net (code "72") (name "unconnected-(U1-PadTXON)") (class "Default")
      (node (ref "U1") (pin "TXON") (pinfunction "TXON_TXON") (pintype "bidirectional"))
    )
    (net (code "73") (name "unconnected-(U2-*3-Pad6)") (class "Default")
      (node (ref "U2") (pin "6") (pinfunction "*3_6") (pintype "bidirectional"))
    )
    (net (code "74") (name "unconnected-(U2-*5-Pad8)") (class "Default")
      (node (ref "U2") (pin "8") (pinfunction "*5_8") (pintype "bidirectional"))
    )
    (net (code "75") (name "unconnected-(U2-*6-Pad9)") (class "Default")
      (node (ref "U2") (pin "9") (pinfunction "*6_9") (pintype "bidirectional"))
    )
    (net (code "76") (name "unconnected-(U2-*9-Pad12)") (class "Default")
      (node (ref "U2") (pin "12") (pinfunction "*9_12") (pintype "bidirectional"))
    )
    (net (code "77") (name "unconnected-(U2-*10-Pad13)") (class "Default")
      (node (ref "U2") (pin "13") (pinfunction "*10_13") (pintype "bidirectional"))
    )
    (net (code "78") (name "unconnected-(U2-*11-Pad14)") (class "Default")
      (node (ref "U2") (pin "14") (pinfunction "*11_14") (pintype "bidirectional"))
    )
    (net (code "79") (name "unconnected-(U2-2-Pad5)") (class "Default")
      (node (ref "U2") (pin "5") (pinfunction "2_5") (pintype "bidirectional"))
    )
    (net (code "80") (name "unconnected-(U2-4-Pad7)") (class "Default")
      (node (ref "U2") (pin "7") (pinfunction "4_7") (pintype "bidirectional"))
    )
    (net (code "81") (name "unconnected-(U2-7-Pad10)") (class "Default")
      (node (ref "U2") (pin "10") (pinfunction "7_10") (pintype "bidirectional"))
    )
    (net (code "82") (name "unconnected-(U2-8-Pad11)") (class "Default")
      (node (ref "U2") (pin "11") (pinfunction "8_11") (pintype "bidirectional"))
    )
    (net (code "83") (name "unconnected-(U2-13-Pad16)") (class "Default")
      (node (ref "U2") (pin "16") (pinfunction "13_16") (pintype "bidirectional"))
    )
    (net (code "84") (name "unconnected-(U2-A0-Pad17)") (class "Default")
      (node (ref "U2") (pin "17") (pinfunction "A0_17") (pintype "bidirectional"))
    )
    (net (code "85") (name "unconnected-(U2-A2-Pad19)") (class "Default")
      (node (ref "U2") (pin "19") (pinfunction "A2_19") (pintype "bidirectional"))
    )
    (net (code "86") (name "unconnected-(U2-A3-Pad20)") (class "Default")
      (node (ref "U2") (pin "20") (pinfunction "A3_20") (pintype "bidirectional"))
    )
    (net (code "87") (name "unconnected-(U2-PadA4)") (class "Default")
      (node (ref "U2") (pin "A4") (pinfunction "A4_A4") (pintype "bidirectional"))
    )
    (net (code "88") (name "unconnected-(U2-PadA5)") (class "Default")
      (node (ref "U2") (pin "A5") (pinfunction "A5_A5") (pintype "bidirectional"))
    )
    (net (code "89") (name "unconnected-(U2-PadA6)") (class "Default")
      (node (ref "U2") (pin "A6") (pinfunction "A6_A6") (pintype "bidirectional"))
    )
    (net (code "90") (name "unconnected-(U2-PadA7)") (class "Default")
      (node (ref "U2") (pin "A7") (pinfunction "A7_A7") (pintype "bidirectional"))
    )
    (net (code "91") (name "unconnected-(U2-RST-Pad3)") (class "Default")
      (node (ref "U2") (pin "3") (pinfunction "RST_3") (pintype "bidirectional"))
    )
    (net (code "92") (name "unconnected-(U3-DRDY-Pad15)") (class "Default")
      (node (ref "U3") (pin "15") (pinfunction "DRDY_15") (pintype "bidirectional"))
    )
    (net (code "93") (name "unconnected-(U3-NC-Pad3)") (class "Default")
      (node (ref "U3") (pin "3") (pinfunction "NC_3") (pintype "bidirectional"))
    )
    (net (code "94") (name "unconnected-(U3-NC-Pad5)") (class "Default")
      (node (ref "U3") (pin "5") (pinfunction "NC_5") (pintype "bidirectional"))
    )
    (net (code "95") (name "unconnected-(U3-NC-Pad6)") (class "Default")
      (node (ref "U3") (pin "6") (pinfunction "NC_6") (pintype "bidirectional"))
    )
    (net (code "96") (name "unconnected-(U3-NC-Pad7)") (class "Default")
      (node (ref "U3") (pin "7") (pinfunction "NC_7") (pintype "bidirectional"))
    )
    (net (code "97") (name "unconnected-(U3-NC-Pad14)") (class "Default")
      (node (ref "U3") (pin "14") (pinfunction "NC_14") (pintype "bidirectional"))
    )
    (net (code "98") (name "unconnected-(U4-Pad20{slash}A6)") (class "Default")
      (node (ref "U4") (pin "20/A6") (pinfunction "20/A6_20/A6") (pintype "bidirectional"))
    )
    (net (code "99") (name "unconnected-(U4-Pad21{slash}A7)") (class "Default")
      (node (ref "U4") (pin "21/A7") (pinfunction "21/A7_21/A7") (pintype "bidirectional"))
    )
    (net (code "100") (name "unconnected-(U4-Pad22{slash}A8)") (class "Default")
      (node (ref "U4") (pin "22/A8") (pinfunction "22/A8_22/A8") (pintype "bidirectional"))
    )
    (net (code "101") (name "unconnected-(U4-PadA10)") (class "Default")
      (node (ref "U4") (pin "A10") (pinfunction "A10_A10") (pintype "bidirectional"))
    )
    (net (code "102") (name "unconnected-(U4-PadA11)") (class "Default")
      (node (ref "U4") (pin "A11") (pinfunction "A11_A11") (pintype "bidirectional"))
    )
    (net (code "103") (name "unconnected-(U4-PadPGM)") (class "Default")
      (node (ref "U4") (pin "PGM") (pinfunction "PGM_PGM") (pintype "bidirectional"))
    )
    (net (code "104") (name "unconnected-(U4-PadRESET)") (class "Default")
      (node (ref "U4") (pin "RESET") (pinfunction "RESET_RESET") (pintype "bidirectional"))
    )
    (net (code "105") (name "unconnected-(U5-INT-Pad12)") (class "Default")
      (node (ref "U5") (pin "12") (pinfunction "INT_12") (pintype "bidirectional"))
    )
    (net (code "106") (name "unconnected-(U7-STATUS-Pad10)") (class "Default")
      (node (ref "U7") (pin "10") (pinfunction "STATUS_10") (pintype "bidirectional"))
    )
  )
)
